# usb-to-serial.net
KiCad netlist of a schematic drawn in EAGLE
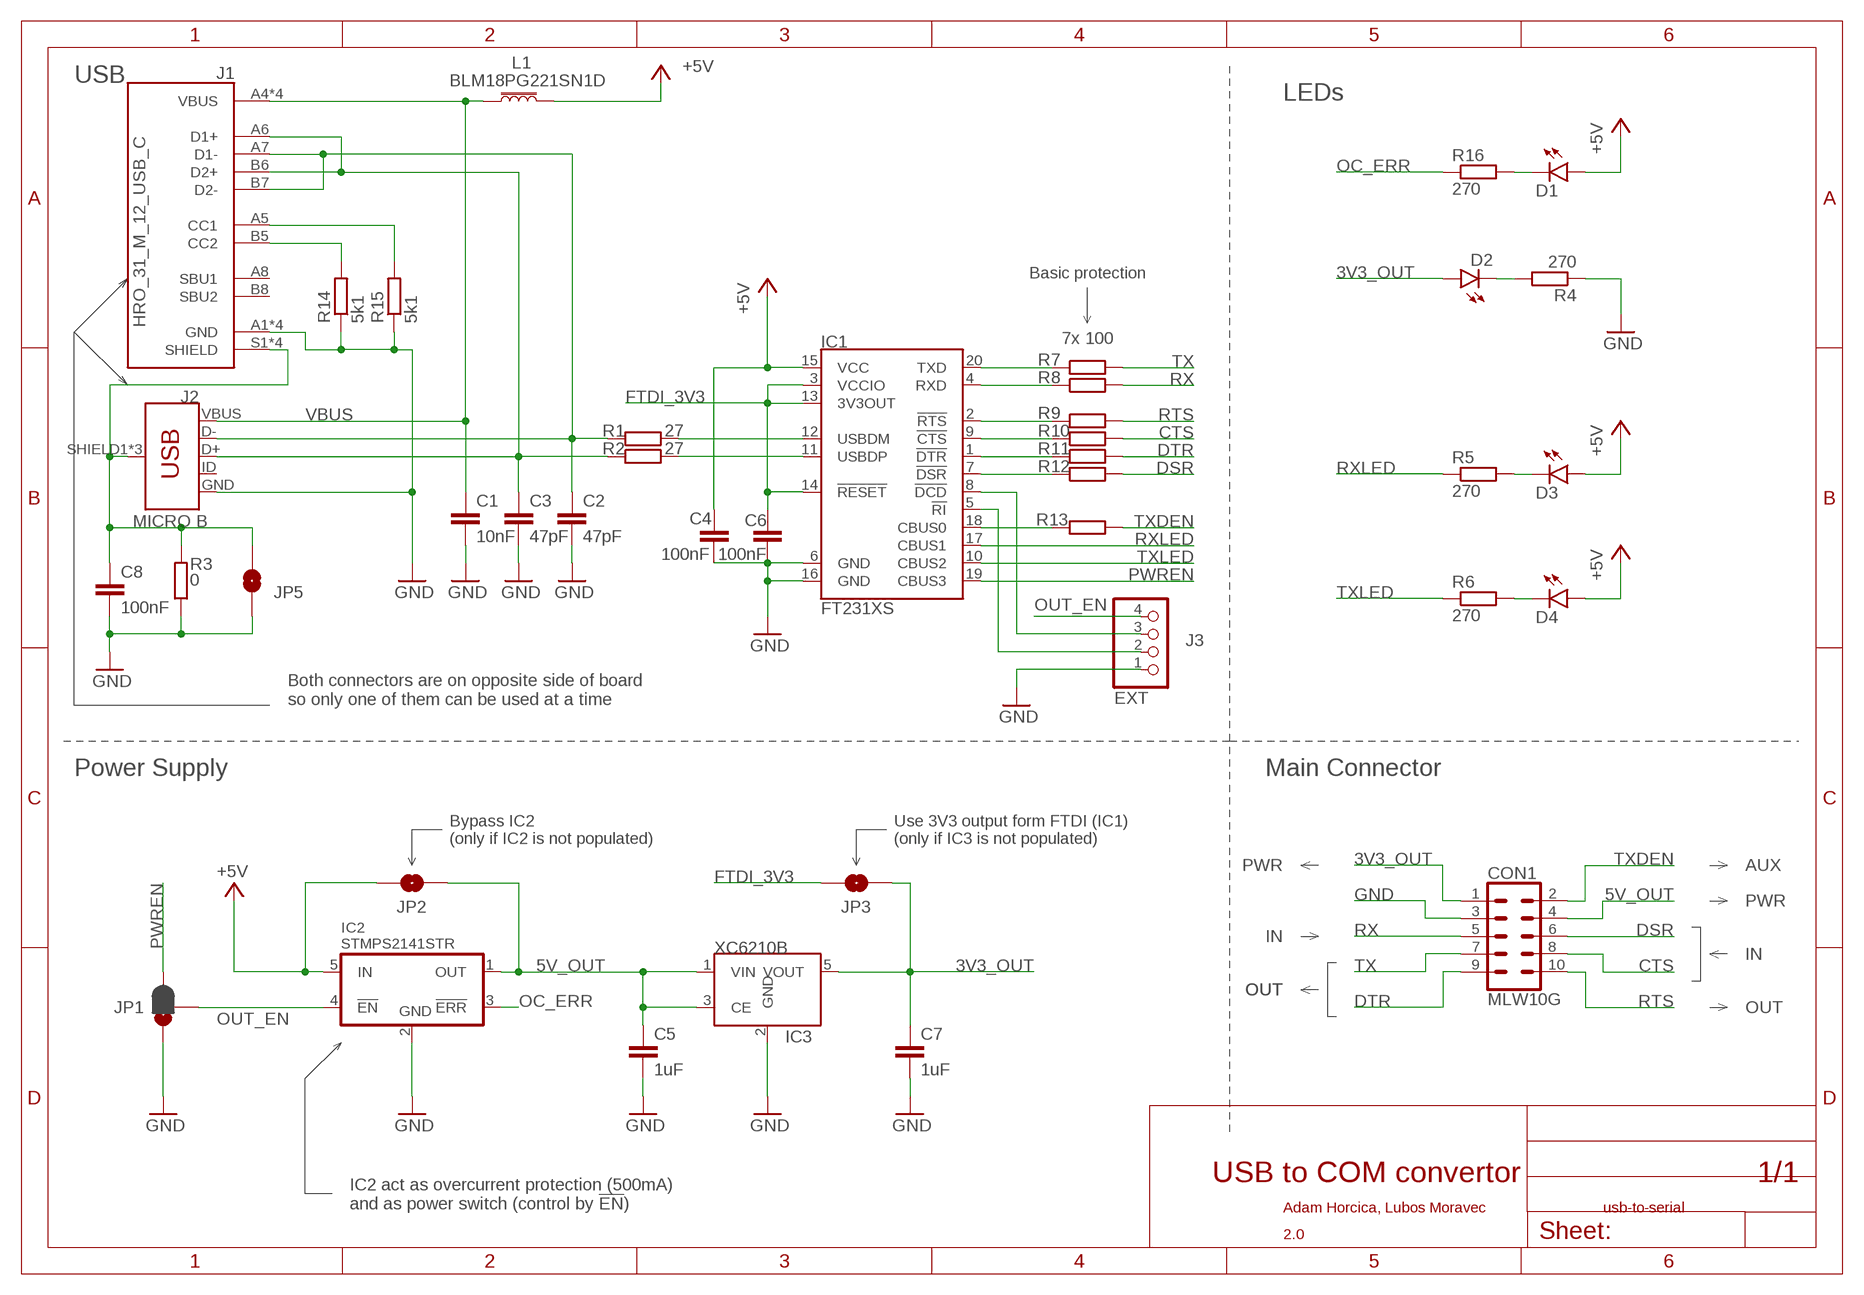
[diagram p0: schematic, sheet 1]

(export (version "E")
  (design (tool "Eeschema 10.0.6"))
  (components
    (comp (ref "C1")
      (value "10nF")
      (footprint "eagle-import:C0603")
      (libsource (lib "eagle-import") (part "C-EUC0603"))
    )
    (comp (ref "C2")
      (value "47pF")
      (footprint "eagle-import:C0603")
      (libsource (lib "eagle-import") (part "C-EUC0603"))
    )
    (comp (ref "C3")
      (value "47pF")
      (footprint "eagle-import:C0603")
      (libsource (lib "eagle-import") (part "C-EUC0603"))
    )
    (comp (ref "C4")
      (value "100nF")
      (footprint "eagle-import:C0603")
      (libsource (lib "eagle-import") (part "C-EUC0603"))
    )
    (comp (ref "C5")
      (value "1uF")
      (footprint "eagle-import:C0603")
      (libsource (lib "eagle-import") (part "C-EUC0603"))
    )
    (comp (ref "C6")
      (value "100nF")
      (footprint "eagle-import:C0603")
      (libsource (lib "eagle-import") (part "C-EUC0603"))
    )
    (comp (ref "C7")
      (value "1uF")
      (footprint "eagle-import:C0603")
      (libsource (lib "eagle-import") (part "C-EUC0603"))
    )
    (comp (ref "C8")
      (value "100nF")
      (footprint "eagle-import:C0603")
      (libsource (lib "eagle-import") (part "C-EUC0603"))
    )
    (comp (ref "CON1")
      (value "MLW10G")
      (footprint "eagle-import:MLW10G")
      (libsource (lib "eagle-import") (part "MLW10G"))
    )
    (comp (ref "D1")
      (value "LEDCHIP-LED0805")
      (footprint "eagle-import:CHIP-LED0805")
      (libsource (lib "eagle-import") (part "LEDCHIP-LED0805"))
    )
    (comp (ref "D2")
      (value "LEDCHIP-LED0805")
      (footprint "eagle-import:CHIP-LED0805")
      (libsource (lib "eagle-import") (part "LEDCHIP-LED0805"))
    )
    (comp (ref "D3")
      (value "LEDCHIP-LED0805")
      (footprint "eagle-import:CHIP-LED0805")
      (libsource (lib "eagle-import") (part "LEDCHIP-LED0805"))
    )
    (comp (ref "D4")
      (value "LEDCHIP-LED0805")
      (footprint "eagle-import:CHIP-LED0805")
      (libsource (lib "eagle-import") (part "LEDCHIP-LED0805"))
    )
    (comp (ref "EXT")
      (value "J3")
      (footprint "eagle-import:1X04")
      (libsource (lib "eagle-import") (part "PINHD-1X4"))
    )
    (comp (ref "IC1")
      (value "FT231XS")
      (footprint "eagle-import:SSOP20_L")
      (libsource (lib "eagle-import") (part "FT231XS"))
    )
    (comp (ref "IC2")
      (value "STMPS2141STR")
      (footprint "eagle-import:SOT23-5")
      (libsource (lib "eagle-import") (part "STMPS2141STR"))
    )
    (comp (ref "IC3")
      (value "XC6210B332MR")
      (footprint "eagle-import:SOT-23-5")
      (libsource (lib "eagle-import") (part "XC6210"))
    )
    (comp (ref "J1")
      (value "HRO_31_M_12_USB_C")
      (footprint "eagle-import:HRO_31_M_12_USB_C")
      (libsource (lib "eagle-import") (part "HRO_31_M_12_USB_C"))
    )
    (comp (ref "J2")
      (value "MICRO B")
      (footprint "eagle-import:USB-B-MICRO-SMD")
      (libsource (lib "eagle-import") (part "USB_MICRO-B_FEMALE-SMT"))
    )
    (comp (ref "JP1")
      (value "JUMPER-SMT_3_1-NC_PASTE_NO-SILK")
      (footprint "eagle-import:SMT-JUMPER_3_1-NC_PASTE_NO-SILK")
      (libsource (lib "eagle-import") (part "JUMPER-SMT_3_1-NC_PASTE_NO-SILK"))
    )
    (comp (ref "JP2")
      (value "JUMPER-SMT_2_NO_NO-SILK")
      (footprint "eagle-import:SMT-JUMPER_2_NO_NO-SILK")
      (libsource (lib "eagle-import") (part "JUMPER-SMT_2_NO_NO-SILK"))
    )
    (comp (ref "JP3")
      (value "JUMPER-SMT_2_NO_NO-SILK")
      (footprint "eagle-import:SMT-JUMPER_2_NO_NO-SILK")
      (libsource (lib "eagle-import") (part "JUMPER-SMT_2_NO_NO-SILK"))
    )
    (comp (ref "JP5")
      (value "JUMPER-SMT_2_NO_NO-SILK")
      (footprint "eagle-import:SMT-JUMPER_2_NO_NO-SILK")
      (libsource (lib "eagle-import") (part "JUMPER-SMT_2_NO_NO-SILK"))
    )
    (comp (ref "L1")
      (value "BLM18PG221SN1D")
      (footprint "eagle-import:0603")
      (libsource (lib "eagle-import") (part "FERRITE_BEAD-0603"))
    )
    (comp (ref "R1")
      (value "27")
      (footprint "eagle-import:R0603")
      (libsource (lib "eagle-import") (part "R-EU_R0603"))
    )
    (comp (ref "R2")
      (value "27")
      (footprint "eagle-import:R0603")
      (libsource (lib "eagle-import") (part "R-EU_R0603"))
    )
    (comp (ref "R3")
      (value "0")
      (footprint "eagle-import:R0603")
      (libsource (lib "eagle-import") (part "R-EU_R0603"))
    )
    (comp (ref "R4")
      (value "270")
      (footprint "eagle-import:R0603")
      (libsource (lib "eagle-import") (part "R-EU_R0603"))
    )
    (comp (ref "R5")
      (value "270")
      (footprint "eagle-import:R0603")
      (libsource (lib "eagle-import") (part "R-EU_R0603"))
    )
    (comp (ref "R6")
      (value "270")
      (footprint "eagle-import:R0603")
      (libsource (lib "eagle-import") (part "R-EU_R0603"))
    )
    (comp (ref "R7")
      (value "100")
      (footprint "eagle-import:R0603")
      (libsource (lib "eagle-import") (part "R-EU_R0603"))
    )
    (comp (ref "R8")
      (value "100")
      (footprint "eagle-import:R0603")
      (libsource (lib "eagle-import") (part "R-EU_R0603"))
    )
    (comp (ref "R9")
      (value "100")
      (footprint "eagle-import:R0603")
      (libsource (lib "eagle-import") (part "R-EU_R0603"))
    )
    (comp (ref "R10")
      (value "100")
      (footprint "eagle-import:R0603")
      (libsource (lib "eagle-import") (part "R-EU_R0603"))
    )
    (comp (ref "R11")
      (value "100")
      (footprint "eagle-import:R0603")
      (libsource (lib "eagle-import") (part "R-EU_R0603"))
    )
    (comp (ref "R12")
      (value "100")
      (footprint "eagle-import:R0603")
      (libsource (lib "eagle-import") (part "R-EU_R0603"))
    )
    (comp (ref "R13")
      (value "100")
      (footprint "eagle-import:R0603")
      (libsource (lib "eagle-import") (part "R-EU_R0603"))
    )
    (comp (ref "R14")
      (value "5k1")
      (footprint "eagle-import:R0603")
      (libsource (lib "eagle-import") (part "R-EU_R0603"))
    )
    (comp (ref "R15")
      (value "5k1")
      (footprint "eagle-import:R0603")
      (libsource (lib "eagle-import") (part "R-EU_R0603"))
    )
    (comp (ref "R16")
      (value "270")
      (footprint "eagle-import:R0603")
      (libsource (lib "eagle-import") (part "R-EU_R0603"))
    )
  )
  (nets
    (net (code "1") (name "+5V") (class "Default")
      (node (ref "C4") (pin "1") (pinfunction "1_1") (pintype "passive"))
      (node (ref "D1") (pin "A") (pinfunction "A_A") (pintype "passive"))
      (node (ref "D3") (pin "A") (pinfunction "A_A") (pintype "passive"))
      (node (ref "D4") (pin "A") (pinfunction "A_A") (pintype "passive"))
      (node (ref "IC1") (pin "15") (pinfunction "VCC_15") (pintype "bidirectional"))
      (node (ref "IC2") (pin "5") (pinfunction "IN_5") (pintype "input"))
      (node (ref "JP2") (pin "1") (pinfunction "1_1") (pintype "passive"))
      (node (ref "L1") (pin "1") (pinfunction "1_1") (pintype "passive"))
    )
    (net (code "2") (name "/3V3_OUT") (class "Default")
      (node (ref "C7") (pin "1") (pinfunction "1_1") (pintype "passive"))
      (node (ref "CON1") (pin "1") (pinfunction "1_1") (pintype "passive"))
      (node (ref "D2") (pin "A") (pinfunction "A_A") (pintype "passive"))
      (node (ref "IC3") (pin "5") (pinfunction "VOUT_5") (pintype "power_in"))
      (node (ref "JP3") (pin "2") (pinfunction "2_2") (pintype "passive"))
    )
    (net (code "3") (name "/5V_OUT") (class "Default")
      (node (ref "C5") (pin "1") (pinfunction "1_1") (pintype "passive"))
      (node (ref "CON1") (pin "4") (pinfunction "4_4") (pintype "passive"))
      (node (ref "IC2") (pin "1") (pinfunction "OUT_1") (pintype "passive"))
      (node (ref "IC3") (pin "1") (pinfunction "VIN_1") (pintype "power_in"))
      (node (ref "IC3") (pin "3") (pinfunction "CE_3") (pintype "power_in"))
      (node (ref "JP2") (pin "2") (pinfunction "2_2") (pintype "passive"))
    )
    (net (code "4") (name "/CTS") (class "Default")
      (node (ref "CON1") (pin "8") (pinfunction "8_8") (pintype "passive"))
      (node (ref "R10") (pin "2") (pinfunction "2_2") (pintype "passive"))
    )
    (net (code "5") (name "/DSR") (class "Default")
      (node (ref "CON1") (pin "6") (pinfunction "6_6") (pintype "passive"))
      (node (ref "R12") (pin "2") (pinfunction "2_2") (pintype "passive"))
    )
    (net (code "6") (name "/DTR") (class "Default")
      (node (ref "CON1") (pin "9") (pinfunction "9_9") (pintype "passive"))
      (node (ref "R11") (pin "2") (pinfunction "2_2") (pintype "passive"))
    )
    (net (code "7") (name "/FTDI_3V3") (class "Default")
      (node (ref "C6") (pin "1") (pinfunction "1_1") (pintype "passive"))
      (node (ref "IC1") (pin "13") (pinfunction "3V3OUT_13") (pintype "bidirectional"))
      (node (ref "IC1") (pin "14") (pinfunction "~{RESET}_14") (pintype "bidirectional"))
      (node (ref "IC1") (pin "3") (pinfunction "VCCIO_3") (pintype "bidirectional"))
      (node (ref "JP3") (pin "1") (pinfunction "1_1") (pintype "passive"))
    )
    (net (code "8") (name "/OC_ERR") (class "Default")
      (node (ref "IC2") (pin "3") (pinfunction "~{ERR}_3") (pintype "output"))
      (node (ref "R16") (pin "1") (pinfunction "1_1") (pintype "passive"))
    )
    (net (code "9") (name "/OUT_EN") (class "Default")
      (node (ref "EXT") (pin "4") (pinfunction "4_4") (pintype "passive"))
      (node (ref "IC2") (pin "4") (pinfunction "~{EN}_4") (pintype "passive"))
      (node (ref "JP1") (pin "2") (pinfunction "2_2") (pintype "passive"))
    )
    (net (code "10") (name "/PWREN") (class "Default")
      (node (ref "IC1") (pin "19") (pinfunction "CBUS3_19") (pintype "bidirectional"))
      (node (ref "JP1") (pin "3") (pinfunction "3_3") (pintype "passive"))
    )
    (net (code "11") (name "/RTS") (class "Default")
      (node (ref "CON1") (pin "10") (pinfunction "10_10") (pintype "passive"))
      (node (ref "R9") (pin "2") (pinfunction "2_2") (pintype "passive"))
    )
    (net (code "12") (name "/RX") (class "Default")
      (node (ref "CON1") (pin "5") (pinfunction "5_5") (pintype "passive"))
      (node (ref "R8") (pin "2") (pinfunction "2_2") (pintype "passive"))
    )
    (net (code "13") (name "/RXLED") (class "Default")
      (node (ref "IC1") (pin "17") (pinfunction "CBUS1_17") (pintype "bidirectional"))
      (node (ref "R5") (pin "1") (pinfunction "1_1") (pintype "passive"))
    )
    (net (code "14") (name "/TX") (class "Default")
      (node (ref "CON1") (pin "7") (pinfunction "7_7") (pintype "passive"))
      (node (ref "R7") (pin "2") (pinfunction "2_2") (pintype "passive"))
    )
    (net (code "15") (name "/TXDEN") (class "Default")
      (node (ref "CON1") (pin "2") (pinfunction "2_2") (pintype "passive"))
      (node (ref "R13") (pin "2") (pinfunction "2_2") (pintype "passive"))
    )
    (net (code "16") (name "/TXLED") (class "Default")
      (node (ref "IC1") (pin "10") (pinfunction "CBUS2_10") (pintype "bidirectional"))
      (node (ref "R6") (pin "1") (pinfunction "1_1") (pintype "passive"))
    )
    (net (code "17") (name "/VBUS") (class "Default")
      (node (ref "C1") (pin "1") (pinfunction "1_1") (pintype "passive"))
      (node (ref "J1") (pin "A4") (pinfunction "VBUS_A4") (pintype "passive"))
      (node (ref "J1") (pin "A9") (pinfunction "VBUS_A9") (pintype "passive"))
      (node (ref "J1") (pin "B4") (pinfunction "VBUS_B4") (pintype "passive"))
      (node (ref "J1") (pin "B9") (pinfunction "VBUS_B9") (pintype "passive"))
      (node (ref "J2") (pin "VBUS") (pinfunction "VBUS_VBUS") (pintype "power_in"))
      (node (ref "L1") (pin "2") (pinfunction "2_2") (pintype "passive"))
    )
    (net (code "18") (name "GND") (class "Default")
      (node (ref "C1") (pin "2") (pinfunction "2_2") (pintype "passive"))
      (node (ref "C2") (pin "2") (pinfunction "2_2") (pintype "passive"))
      (node (ref "C3") (pin "2") (pinfunction "2_2") (pintype "passive"))
      (node (ref "C4") (pin "2") (pinfunction "2_2") (pintype "passive"))
      (node (ref "C5") (pin "2") (pinfunction "2_2") (pintype "passive"))
      (node (ref "C6") (pin "2") (pinfunction "2_2") (pintype "passive"))
      (node (ref "C7") (pin "2") (pinfunction "2_2") (pintype "passive"))
      (node (ref "C8") (pin "2") (pinfunction "2_2") (pintype "passive"))
      (node (ref "CON1") (pin "3") (pinfunction "3_3") (pintype "passive"))
      (node (ref "EXT") (pin "1") (pinfunction "1_1") (pintype "passive"))
      (node (ref "IC1") (pin "16") (pinfunction "GND_16") (pintype "bidirectional"))
      (node (ref "IC1") (pin "6") (pinfunction "GND_6") (pintype "bidirectional"))
      (node (ref "IC2") (pin "2") (pinfunction "GND_2") (pintype "power_in"))
      (node (ref "IC3") (pin "2") (pinfunction "GND_2") (pintype "power_in"))
      (node (ref "J1") (pin "A1") (pinfunction "GND_A1") (pintype "passive"))
      (node (ref "J1") (pin "A12") (pinfunction "GND_A12") (pintype "passive"))
      (node (ref "J1") (pin "B1") (pinfunction "GND_B1") (pintype "passive"))
      (node (ref "J1") (pin "B12") (pinfunction "GND_B12") (pintype "passive"))
      (node (ref "J2") (pin "GND") (pinfunction "GND_GND") (pintype "power_in"))
      (node (ref "JP1") (pin "1") (pinfunction "1_1") (pintype "passive"))
      (node (ref "JP5") (pin "1") (pinfunction "1_1") (pintype "passive"))
      (node (ref "R14") (pin "1") (pinfunction "1_1") (pintype "passive"))
      (node (ref "R15") (pin "1") (pinfunction "1_1") (pintype "passive"))
      (node (ref "R3") (pin "1") (pinfunction "1_1") (pintype "passive"))
      (node (ref "R4") (pin "1") (pinfunction "1_1") (pintype "passive"))
    )
    (net (code "19") (name "Net-(C8-Pad1)") (class "Default")
      (node (ref "C8") (pin "1") (pinfunction "1_1") (pintype "passive"))
      (node (ref "J1") (pin "S1") (pinfunction "SHIELD_S1") (pintype "passive"))
      (node (ref "J1") (pin "S2") (pinfunction "SHIELD_S2") (pintype "passive"))
      (node (ref "J1") (pin "S3") (pinfunction "SHIELD_S3") (pintype "passive"))
      (node (ref "J1") (pin "S4") (pinfunction "SHIELD_S4") (pintype "passive"))
      (node (ref "J2") (pin "SHIELD1") (pinfunction "SHIELD_SHIELD1") (pintype "bidirectional"))
      (node (ref "J2") (pin "SHIELD2") (pinfunction "SHIELD_SHIELD2") (pintype "bidirectional"))
      (node (ref "J2") (pin "SHIELD3") (pinfunction "SHIELD_SHIELD3") (pintype "bidirectional"))
      (node (ref "JP5") (pin "2") (pinfunction "2_2") (pintype "passive"))
      (node (ref "R3") (pin "2") (pinfunction "2_2") (pintype "passive"))
    )
    (net (code "20") (name "Net-(D1-PadC)") (class "Default")
      (node (ref "D1") (pin "C") (pinfunction "C_C") (pintype "passive"))
      (node (ref "R16") (pin "2") (pinfunction "2_2") (pintype "passive"))
    )
    (net (code "21") (name "Net-(D2-PadC)") (class "Default")
      (node (ref "D2") (pin "C") (pinfunction "C_C") (pintype "passive"))
      (node (ref "R4") (pin "2") (pinfunction "2_2") (pintype "passive"))
    )
    (net (code "22") (name "Net-(D3-PadC)") (class "Default")
      (node (ref "D3") (pin "C") (pinfunction "C_C") (pintype "passive"))
      (node (ref "R5") (pin "2") (pinfunction "2_2") (pintype "passive"))
    )
    (net (code "23") (name "Net-(D4-PadC)") (class "Default")
      (node (ref "D4") (pin "C") (pinfunction "C_C") (pintype "passive"))
      (node (ref "R6") (pin "2") (pinfunction "2_2") (pintype "passive"))
    )
    (net (code "24") (name "Net-(IC1-CBUS0)") (class "Default")
      (node (ref "IC1") (pin "18") (pinfunction "CBUS0_18") (pintype "bidirectional"))
      (node (ref "R13") (pin "1") (pinfunction "1_1") (pintype "passive"))
    )
    (net (code "25") (name "Net-(IC1-RXD)") (class "Default")
      (node (ref "IC1") (pin "4") (pinfunction "RXD_4") (pintype "bidirectional"))
      (node (ref "R8") (pin "1") (pinfunction "1_1") (pintype "passive"))
    )
    (net (code "26") (name "Net-(IC1-TXD)") (class "Default")
      (node (ref "IC1") (pin "20") (pinfunction "TXD_20") (pintype "bidirectional"))
      (node (ref "R7") (pin "1") (pinfunction "1_1") (pintype "passive"))
    )
    (net (code "27") (name "Net-(IC1-USBDM)") (class "Default")
      (node (ref "IC1") (pin "12") (pinfunction "USBDM_12") (pintype "bidirectional"))
      (node (ref "R1") (pin "2") (pinfunction "2_2") (pintype "passive"))
    )
    (net (code "28") (name "Net-(IC1-USBDP)") (class "Default")
      (node (ref "IC1") (pin "11") (pinfunction "USBDP_11") (pintype "bidirectional"))
      (node (ref "R2") (pin "2") (pinfunction "2_2") (pintype "passive"))
    )
    (net (code "29") (name "Net-(IC1-~{CTS})") (class "Default")
      (node (ref "IC1") (pin "9") (pinfunction "~{CTS}_9") (pintype "bidirectional"))
      (node (ref "R10") (pin "1") (pinfunction "1_1") (pintype "passive"))
    )
    (net (code "30") (name "Net-(IC1-~{DCD})") (class "Default")
      (node (ref "EXT") (pin "3") (pinfunction "3_3") (pintype "passive"))
      (node (ref "IC1") (pin "8") (pinfunction "~{DCD}_8") (pintype "bidirectional"))
    )
    (net (code "31") (name "Net-(IC1-~{DSR})") (class "Default")
      (node (ref "IC1") (pin "7") (pinfunction "~{DSR}_7") (pintype "bidirectional"))
      (node (ref "R12") (pin "1") (pinfunction "1_1") (pintype "passive"))
    )
    (net (code "32") (name "Net-(IC1-~{DTR})") (class "Default")
      (node (ref "IC1") (pin "1") (pinfunction "~{DTR}_1") (pintype "bidirectional"))
      (node (ref "R11") (pin "1") (pinfunction "1_1") (pintype "passive"))
    )
    (net (code "33") (name "Net-(IC1-~{RI})") (class "Default")
      (node (ref "EXT") (pin "2") (pinfunction "2_2") (pintype "passive"))
      (node (ref "IC1") (pin "5") (pinfunction "~{RI}_5") (pintype "bidirectional"))
    )
    (net (code "34") (name "Net-(IC1-~{RTS})") (class "Default")
      (node (ref "IC1") (pin "2") (pinfunction "~{RTS}_2") (pintype "bidirectional"))
      (node (ref "R9") (pin "1") (pinfunction "1_1") (pintype "passive"))
    )
    (net (code "35") (name "Net-(J1-CC1)") (class "Default")
      (node (ref "J1") (pin "A5") (pinfunction "CC1_A5") (pintype "passive"))
      (node (ref "R15") (pin "2") (pinfunction "2_2") (pintype "passive"))
    )
    (net (code "36") (name "Net-(J1-CC2)") (class "Default")
      (node (ref "J1") (pin "B5") (pinfunction "CC2_B5") (pintype "passive"))
      (node (ref "R14") (pin "2") (pinfunction "2_2") (pintype "passive"))
    )
    (net (code "37") (name "Net-(J1-D1+)") (class "Default")
      (node (ref "C3") (pin "1") (pinfunction "1_1") (pintype "passive"))
      (node (ref "J1") (pin "A6") (pinfunction "D1+_A6") (pintype "passive"))
      (node (ref "J1") (pin "B6") (pinfunction "D2+_B6") (pintype "passive"))
      (node (ref "J2") (pin "D+") (pinfunction "D+_D+") (pintype "bidirectional"))
      (node (ref "R2") (pin "1") (pinfunction "1_1") (pintype "passive"))
    )
    (net (code "38") (name "Net-(J1-D1-)") (class "Default")
      (node (ref "C2") (pin "1") (pinfunction "1_1") (pintype "passive"))
      (node (ref "J1") (pin "A7") (pinfunction "D1-_A7") (pintype "passive"))
      (node (ref "J1") (pin "B7") (pinfunction "D2-_B7") (pintype "passive"))
      (node (ref "J2") (pin "D-") (pinfunction "D-_D-") (pintype "bidirectional"))
      (node (ref "R1") (pin "1") (pinfunction "1_1") (pintype "passive"))
    )
    (net (code "39") (name "unconnected-(J1-SBU1-PadA8)") (class "Default")
      (node (ref "J1") (pin "A8") (pinfunction "SBU1_A8") (pintype "passive"))
    )
    (net (code "40") (name "unconnected-(J1-SBU2-PadB8)") (class "Default")
      (node (ref "J1") (pin "B8") (pinfunction "SBU2_B8") (pintype "passive"))
    )
    (net (code "41") (name "unconnected-(J2-PadID)") (class "Default")
      (node (ref "J2") (pin "ID") (pinfunction "ID_ID") (pintype "bidirectional"))
    )
  )
)
